# design.net
KiCad netlist of a schematic drawn in Altium Designer
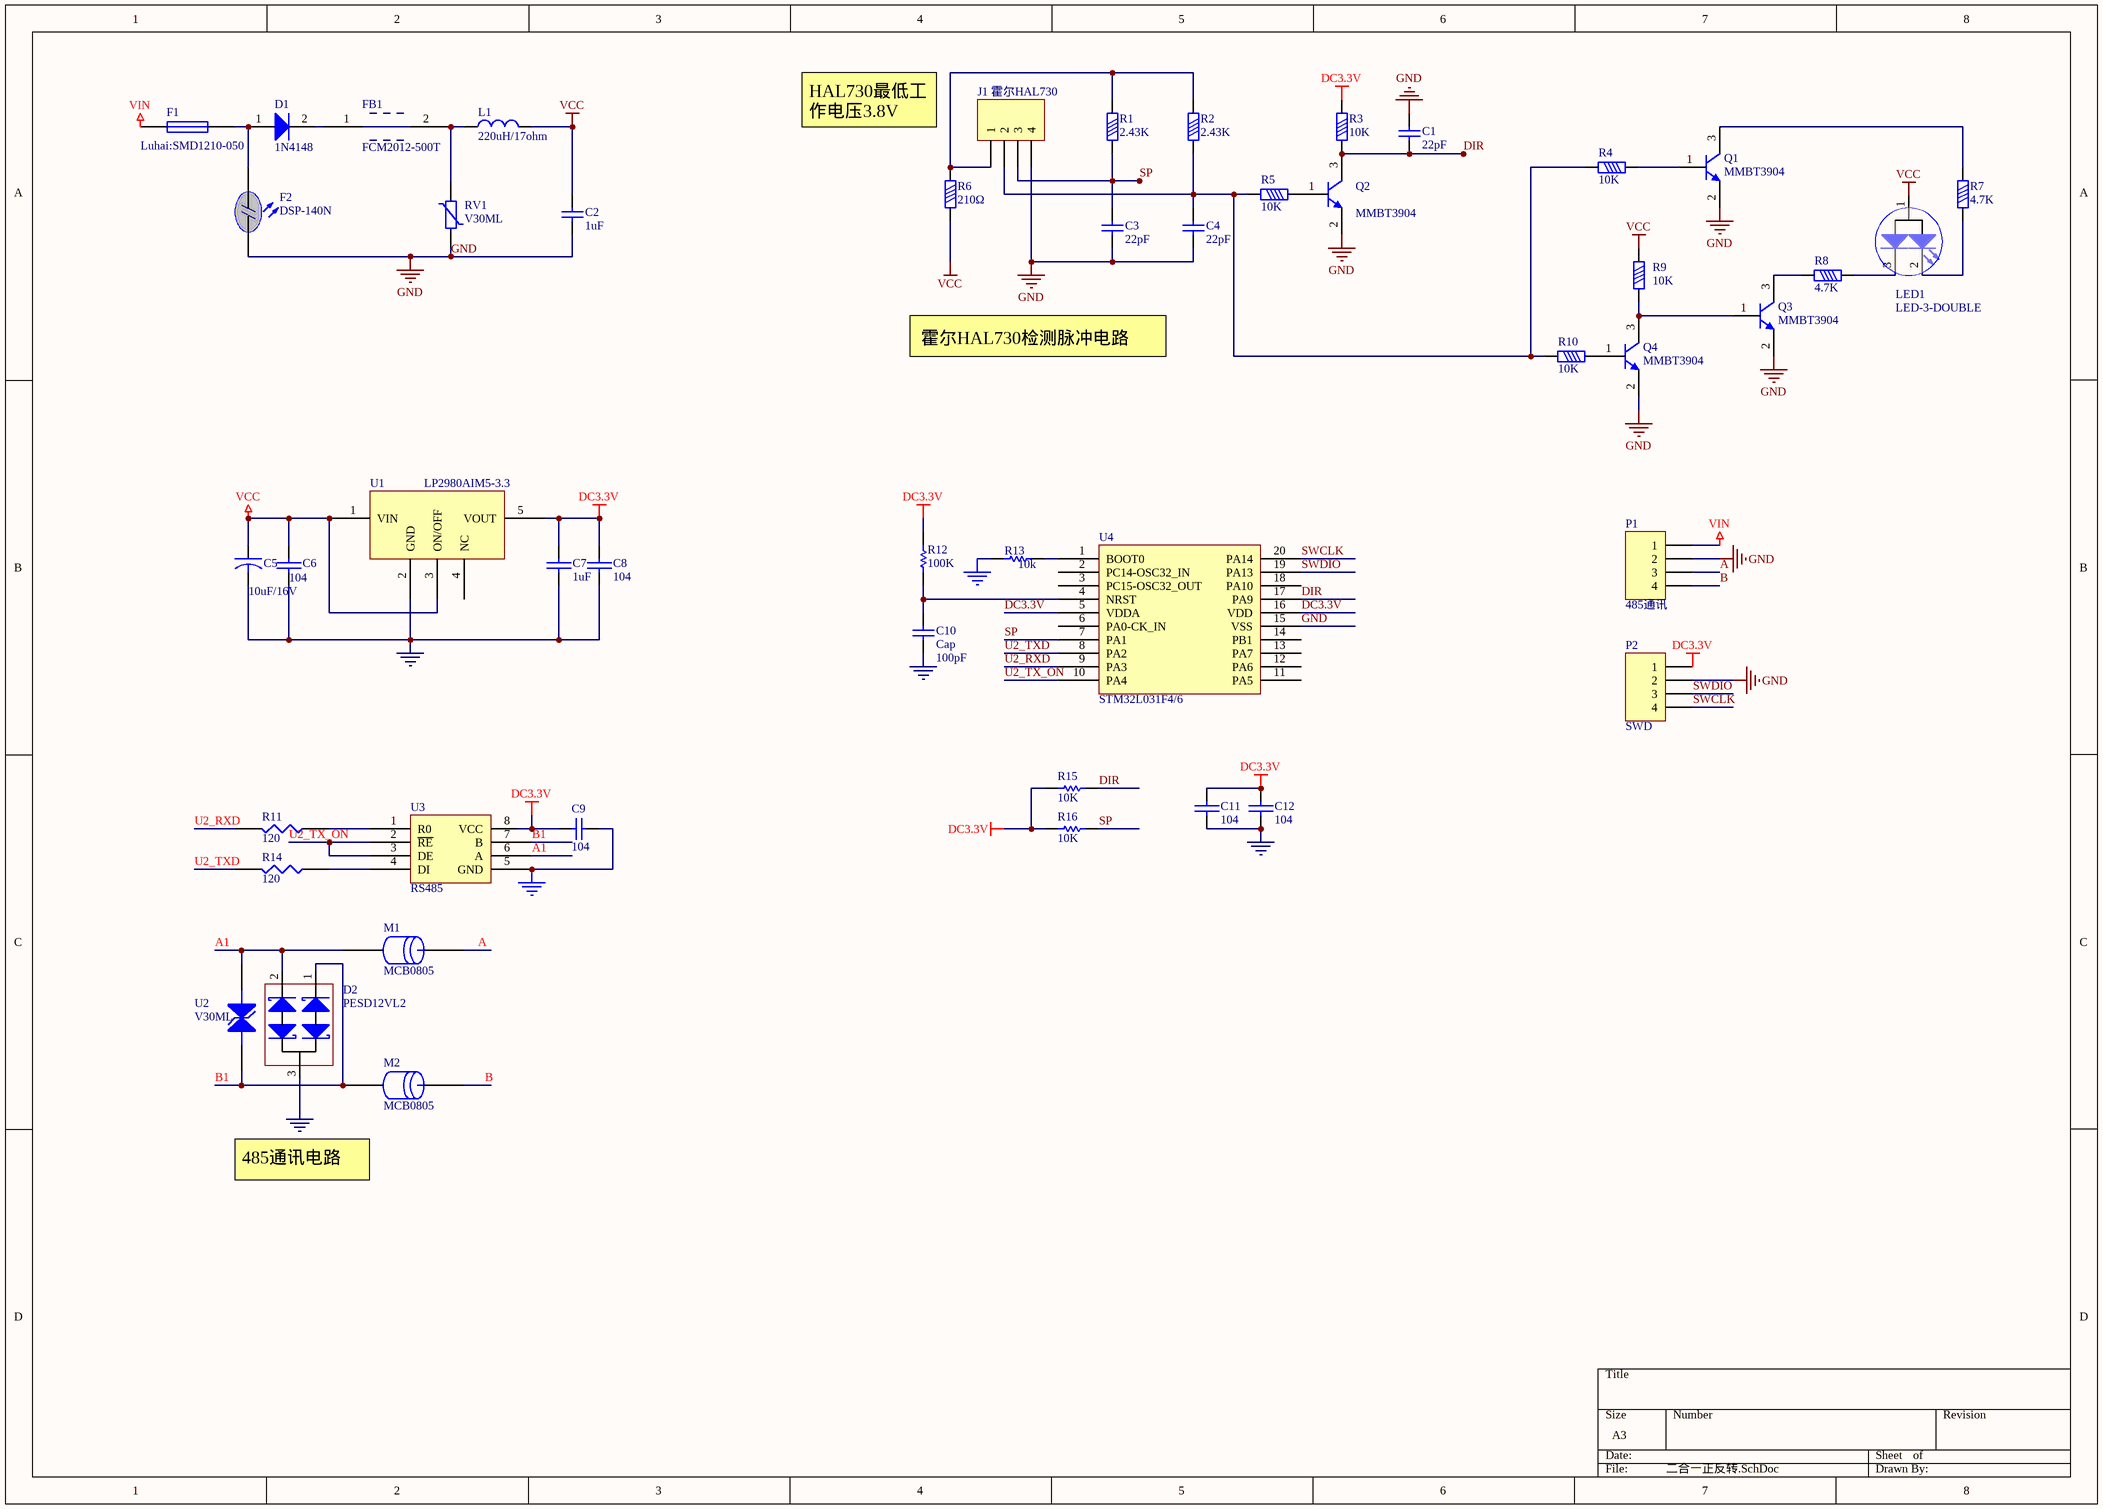
[diagram p0: 二合一正反转.SchDoc]

(export (version "E")
  (design (tool "Eeschema 10.0.6"))
  (components
    (comp (ref "C1")
      (value "22pF")
      (footprint "0603C")
      (description "Polarized Capacitor (Radial)")
      (fields (field (name "Comment") "Cap Chip 0603") (field (name "PUBLISHER") "Altium Limited"))
      (libsource (lib "EButterflyIntegratedLibrary") (part "Cap Chip 0603"))
    )
    (comp (ref "C2")
      (value "1uF")
      (footprint "0805C")
      (description "Polarized Capacitor (Radial)")
      (fields (field (name "PUBLISHER") "Altium Limited"))
      (libsource (lib "EButterflyIntegratedLibrary") (part "Cap Chip 0805"))
    )
    (comp (ref "C3")
      (value "22pF")
      (footprint "0603C")
      (description "Polarized Capacitor (Radial)")
      (fields (field (name "Comment") "Cap Chip 0603") (field (name "PUBLISHER") "Altium Limited"))
      (libsource (lib "EButterflyIntegratedLibrary") (part "Cap Chip 0603"))
    )
    (comp (ref "C4")
      (value "22pF")
      (footprint "0603C")
      (description "Polarized Capacitor (Radial)")
      (fields (field (name "Comment") "Cap Chip 0603") (field (name "PUBLISHER") "Altium Limited"))
      (libsource (lib "EButterflyIntegratedLibrary") (part "Cap Chip 0603"))
    )
    (comp (ref "C5")
      (value "10uF/16V")
      (footprint "A3216")
      (description "Capacitor")
      (libsource (lib "*") (part "CAPACITOR"))
    )
    (comp (ref "C6")
      (value "104")
      (footprint "0603C")
      (description "Capacitor")
      (libsource (lib "*") (part "CAP"))
    )
    (comp (ref "C7")
      (value "1uF")
      (footprint "0603C")
      (description "Capacitor")
      (libsource (lib "*") (part "CAP"))
    )
    (comp (ref "C8")
      (value "104")
      (footprint "0603C")
      (description "Capacitor")
      (libsource (lib "*") (part "CAP"))
    )
    (comp (ref "C9")
      (value "104")
      (footprint "0603C")
      (description "Capacitor")
      (fields (field (name "PUBLISHER") "*"))
      (libsource (lib "*") (part "Cap"))
    )
    (comp (ref "C10")
      (value "Cap")
      (footprint "0603C")
      (description "Capacitor")
      (fields (field (name "ALTIUM_VALUE") "100pF") (field (name "PUBLISHER") "Altium Limited"))
      (libsource (lib "Miscellaneous Devices") (part "Cap"))
    )
    (comp (ref "C11")
      (value "104")
      (footprint "0603C")
      (description "Capacitor")
      (libsource (lib "*") (part "CAP"))
    )
    (comp (ref "C12")
      (value "104")
      (footprint "0603C")
      (description "Capacitor")
      (libsource (lib "*") (part "CAP"))
    )
    (comp (ref "D1")
      (value "1N4148")
      (footprint "1N4148")
      (libsource (lib "Integrated_Library1") (part "1N4148"))
    )
    (comp (ref "D2") (value "PESD12VL2") (footprint "SOT23") (libsource (lib "lewis lib") (part "TVS")))
    (comp (ref "F1")
      (value "Luhai:SMD1210-050")
      (footprint "1210R")
      (description "Fuse")
      (fields (field (name "PUBLISHER") "Altium Limited"))
      (libsource (lib "Miscellaneous Devices") (part "Fuse 1"))
    )
    (comp (ref "F2")
      (value "DSP-140N")
      (footprint "DSP")
      (libsource (lib "Integrated_Library1") (part "DSP-140N"))
    )
    (comp (ref "FB1")
      (value "FCM2012-500T")
      (footprint "FB")
      (libsource (lib "Integrated_Library1") (part "FCM2012-500T"))
    )
    (comp (ref "J1")
      (value "霍尔HAL730")
      (footprint "HDR1X4")
      (description "Header, 4-Pin")
      (fields (field (name "PUBLISHER") "Altium Limited"))
      (libsource (lib "EButterflyIntegratedLibrary") (part "Header 4"))
    )
    (comp (ref "L1")
      (value "220uH/17ohm")
      (footprint "220uH/17ohm")
      (libsource (lib "Integrated_Library1") (part "220uH/17ohm"))
    )
    (comp (ref "LED1")
      (value "LED-3-DOUBLE")
      (footprint "LED-R3-H5-DOUBLE")
      (libsource (lib "Integrated_Library1") (part "DOUB-LED"))
    )
    (comp (ref "M1")
      (value "MCB0805")
      (footprint "0805F")
      (description "magnetic bead")
      (libsource (lib "lewis lib") (part "MAGNETIC BEAD"))
    )
    (comp (ref "M2")
      (value "MCB0805")
      (footprint "0805F")
      (description "magnetic bead")
      (libsource (lib "lewis lib") (part "MAGNETIC BEAD"))
    )
    (comp (ref "P1")
      (value "485通讯")
      (footprint "HDR1X4")
      (description "Header, 4-Pin, Right Angle")
      (fields (field (name "PUBLISHER") "Altium Limited"))
      (libsource (lib "Miscellaneous Connectors") (part "Header 4H"))
    )
    (comp (ref "P2")
      (value "SWD")
      (footprint "MHDR1X4")
      (description "Header, 4-Pin")
      (fields (field (name "PUBLISHER") "Altium Limited"))
      (libsource (lib "Miscellaneous Connectors") (part "Header 4"))
    )
    (comp (ref "Q1")
      (value "MMBT3904")
      (footprint "MMBT3904")
      (libsource (lib "Integrated_Library1") (part "MMBT3904"))
    )
    (comp (ref "Q2")
      (value "MMBT3904")
      (footprint "MMBT3904")
      (libsource (lib "Integrated_Library1") (part "MMBT3904"))
    )
    (comp (ref "Q3")
      (value "MMBT3904")
      (footprint "MMBT3904")
      (libsource (lib "Integrated_Library1") (part "MMBT3904"))
    )
    (comp (ref "Q4")
      (value "MMBT3904")
      (footprint "MMBT3904")
      (libsource (lib "Integrated_Library1") (part "MMBT3904"))
    )
    (comp (ref "R1")
      (value "2.43K")
      (footprint "0603C")
      (description "Resistor")
      (fields (field (name "Comment") "Resistor Chip 0603") (field (name "PUBLISHER") "Altium Limited"))
      (libsource (lib "") (part "Resistor Chip 0603_1"))
    )
    (comp (ref "R2")
      (value "2.43K")
      (footprint "0603C")
      (description "Resistor")
      (fields (field (name "Comment") "Resistor Chip 0603") (field (name "PUBLISHER") "Altium Limited"))
      (libsource (lib "") (part "Resistor Chip 0603_1"))
    )
    (comp (ref "R3")
      (value "10K")
      (footprint "0603C")
      (description "Resistor")
      (fields (field (name "Comment") "Resistor Chip 0603") (field (name "PUBLISHER") "Altium Limited"))
      (libsource (lib "") (part "Resistor Chip 0603_1"))
    )
    (comp (ref "R4")
      (value "10K")
      (footprint "0603C")
      (description "Resistor")
      (fields (field (name "Comment") "Resistor Chip 0603") (field (name "PUBLISHER") "Altium Limited"))
      (libsource (lib "EButterflyIntegratedLibrary") (part "Resistor Chip 0603"))
    )
    (comp (ref "R5")
      (value "10K")
      (footprint "0603C")
      (description "Resistor")
      (fields (field (name "Comment") "Resistor Chip 0603") (field (name "PUBLISHER") "Altium Limited"))
      (libsource (lib "EButterflyIntegratedLibrary") (part "Resistor Chip 0603"))
    )
    (comp (ref "R6")
      (value "210Ω")
      (footprint "0603C")
      (description "Resistor")
      (fields (field (name "Comment") "Resistor Chip 0603") (field (name "PUBLISHER") "Altium Limited"))
      (libsource (lib "") (part "Resistor Chip 0603_2"))
    )
    (comp (ref "R7")
      (value "4.7K")
      (footprint "0603C")
      (description "Resistor")
      (fields (field (name "Comment") "Resistor Chip 0603") (field (name "PUBLISHER") "Altium Limited"))
      (libsource (lib "") (part "Resistor Chip 0603_2"))
    )
    (comp (ref "R8")
      (value "4.7K")
      (footprint "0603C")
      (description "Resistor")
      (fields (field (name "Comment") "Resistor Chip 0603") (field (name "PUBLISHER") "Altium Limited"))
      (libsource (lib "EButterflyIntegratedLibrary") (part "Resistor Chip 0603"))
    )
    (comp (ref "R9")
      (value "10K")
      (footprint "0603C")
      (description "Resistor")
      (fields (field (name "Comment") "Resistor Chip 0603") (field (name "PUBLISHER") "Altium Limited"))
      (libsource (lib "") (part "Resistor Chip 0603_2"))
    )
    (comp (ref "R10")
      (value "10K")
      (footprint "0603C")
      (description "Resistor")
      (fields (field (name "Comment") "Resistor Chip 0603") (field (name "PUBLISHER") "Altium Limited"))
      (libsource (lib "EButterflyIntegratedLibrary") (part "Resistor Chip 0603"))
    )
    (comp (ref "R11") (value "120") (footprint "0603R") (libsource (lib "*") (part "RES1")))
    (comp (ref "R12")
      (value "100K")
      (footprint "0603R")
      (description "Resistor")
      (fields (field (name "PUBLISHER") "Altium Limited"))
      (libsource (lib "Miscellaneous Devices") (part "Res1"))
    )
    (comp (ref "R13")
      (value "10k")
      (footprint "0603R")
      (description "Resistor")
      (fields (field (name "PUBLISHER") "Altium Limited"))
      (libsource (lib "Miscellaneous Devices") (part "Res1"))
    )
    (comp (ref "R14") (value "120") (footprint "0603R") (libsource (lib "*") (part "RES1")))
    (comp (ref "R15")
      (value "10K")
      (footprint "0603R")
      (description "Resistor")
      (fields (field (name "PUBLISHER") "Altium Limited"))
      (libsource (lib "Miscellaneous Devices") (part "Res1"))
    )
    (comp (ref "R16")
      (value "10K")
      (footprint "0603R")
      (description "Resistor")
      (fields (field (name "PUBLISHER") "Altium Limited"))
      (libsource (lib "Miscellaneous Devices") (part "Res1"))
    )
    (comp (ref "RV1") (value "V30ML") (footprint "RV") (libsource (lib "Integrated_Library1") (part "V30ML")))
    (comp (ref "U1")
      (value "LP2980AIM5-3.3")
      (footprint "SOT-23-5")
      (libsource (lib "lewis lib") (part "LP2980AIM5-3.3"))
    )
    (comp (ref "U2") (value "V30ML") (footprint "0805C-E") (libsource (lib "*") (part "V30ML")))
    (comp (ref "U3") (value "RS485") (footprint "SO-8") (libsource (lib "*") (part "RS485")))
    (comp (ref "U4")
      (value "STM32L031F4/6")
      (footprint "TSSOP20")
      (libsource (lib "lewis lib") (part "STM32L031F4/6"))
    )
  )
  (nets
    (net (code "1") (name "/A") (class "Default")
      (node (ref "M1") (pin "2") (pintype "passive"))
      (node (ref "P1") (pin "3") (pinfunction "3_3") (pintype "passive"))
    )
    (net (code "2") (name "/A1") (class "Default")
      (node (ref "D2") (pin "2") (pinfunction "2_2") (pintype "passive"))
      (node (ref "M1") (pin "1") (pintype "passive"))
      (node (ref "U2") (pin "2") (pinfunction "2_2") (pintype "passive"))
      (node (ref "U3") (pin "6") (pinfunction "A_6") (pintype "passive"))
    )
    (net (code "3") (name "/B") (class "Default")
      (node (ref "M2") (pin "2") (pintype "passive"))
      (node (ref "P1") (pin "4") (pinfunction "4_4") (pintype "passive"))
    )
    (net (code "4") (name "/B1") (class "Default")
      (node (ref "D2") (pin "1") (pinfunction "1_1") (pintype "passive"))
      (node (ref "M2") (pin "1") (pintype "passive"))
      (node (ref "U2") (pin "1") (pinfunction "1_1") (pintype "passive"))
      (node (ref "U3") (pin "7") (pinfunction "B_7") (pintype "passive"))
    )
    (net (code "5") (name "/DIR") (class "Default")
      (node (ref "C1") (pin "1") (pinfunction "1_1") (pintype "passive"))
      (node (ref "Q2") (pin "3") (pinfunction "C_3") (pintype "passive"))
      (node (ref "R15") (pin "1") (pinfunction "1_1") (pintype "passive"))
      (node (ref "R3") (pin "1") (pinfunction "1_1") (pintype "passive"))
      (node (ref "U4") (pin "17") (pinfunction "PA9_17") (pintype "passive"))
    )
    (net (code "6") (name "/SP") (class "Default")
      (node (ref "C3") (pin "2") (pinfunction "2_2") (pintype "passive"))
      (node (ref "J1") (pin "3") (pinfunction "3_3") (pintype "passive"))
      (node (ref "R1") (pin "1") (pinfunction "1_1") (pintype "passive"))
      (node (ref "R16") (pin "2") (pinfunction "2_2") (pintype "passive"))
      (node (ref "U4") (pin "7") (pinfunction "PA1_7") (pintype "passive"))
    )
    (net (code "7") (name "/SWCLK") (class "Default")
      (node (ref "P2") (pin "4") (pinfunction "4_4") (pintype "passive"))
      (node (ref "U4") (pin "20") (pinfunction "PA14_20") (pintype "passive"))
    )
    (net (code "8") (name "/SWDIO") (class "Default")
      (node (ref "P2") (pin "3") (pinfunction "3_3") (pintype "passive"))
      (node (ref "U4") (pin "19") (pinfunction "PA13_19") (pintype "passive"))
    )
    (net (code "9") (name "/U2_RXD") (class "Default")
      (node (ref "R11") (pin "2") (pinfunction "2_2") (pintype "passive"))
      (node (ref "U4") (pin "9") (pinfunction "PA3_9") (pintype "passive"))
    )
    (net (code "10") (name "/U2_TXD") (class "Default")
      (node (ref "R14") (pin "2") (pinfunction "2_2") (pintype "passive"))
      (node (ref "U4") (pin "8") (pinfunction "PA2_8") (pintype "passive"))
    )
    (net (code "11") (name "/U2_TX_ON") (class "Default")
      (node (ref "U3") (pin "2") (pinfunction "~{RE}_2") (pintype "passive"))
      (node (ref "U3") (pin "3") (pinfunction "DE_3") (pintype "passive"))
      (node (ref "U4") (pin "10") (pinfunction "PA4_10") (pintype "passive"))
    )
    (net (code "12") (name "DC3.3V") (class "Default")
      (node (ref "C11") (pin "1") (pinfunction "1_1") (pintype "passive"))
      (node (ref "C12") (pin "1") (pinfunction "1_1") (pintype "passive"))
      (node (ref "C7") (pin "1") (pinfunction "1_1") (pintype "passive"))
      (node (ref "C8") (pin "1") (pinfunction "1_1") (pintype "passive"))
      (node (ref "C9") (pin "1") (pinfunction "1_1") (pintype "passive"))
      (node (ref "P2") (pin "1") (pinfunction "1_1") (pintype "passive"))
      (node (ref "R12") (pin "1") (pinfunction "1_1") (pintype "passive"))
      (node (ref "R15") (pin "2") (pinfunction "2_2") (pintype "passive"))
      (node (ref "R16") (pin "1") (pinfunction "1_1") (pintype "passive"))
      (node (ref "R3") (pin "2") (pinfunction "2_2") (pintype "passive"))
      (node (ref "U1") (pin "5") (pinfunction "VOUT_5") (pintype "passive"))
      (node (ref "U3") (pin "8") (pinfunction "VCC_8") (pintype "passive"))
      (node (ref "U4") (pin "16") (pinfunction "VDD_16") (pintype "passive"))
      (node (ref "U4") (pin "5") (pinfunction "VDDA_5") (pintype "passive"))
    )
    (net (code "13") (name "GND") (class "Default")
      (node (ref "C1") (pin "2") (pinfunction "2_2") (pintype "passive"))
      (node (ref "C10") (pin "1") (pinfunction "1_1") (pintype "passive"))
      (node (ref "C11") (pin "2") (pinfunction "2_2") (pintype "passive"))
      (node (ref "C12") (pin "2") (pinfunction "2_2") (pintype "passive"))
      (node (ref "C2") (pin "1") (pinfunction "1_1") (pintype "passive"))
      (node (ref "C3") (pin "1") (pinfunction "1_1") (pintype "passive"))
      (node (ref "C4") (pin "1") (pinfunction "1_1") (pintype "passive"))
      (node (ref "C5") (pin "2") (pinfunction "2_2") (pintype "passive"))
      (node (ref "C6") (pin "2") (pinfunction "2_2") (pintype "passive"))
      (node (ref "C7") (pin "2") (pinfunction "2_2") (pintype "passive"))
      (node (ref "C8") (pin "2") (pinfunction "2_2") (pintype "passive"))
      (node (ref "C9") (pin "2") (pinfunction "2_2") (pintype "passive"))
      (node (ref "D2") (pin "3") (pinfunction "3_3") (pintype "passive"))
      (node (ref "F2") (pin "2") (pinfunction "2_2") (pintype "passive"))
      (node (ref "J1") (pin "4") (pinfunction "4_4") (pintype "passive"))
      (node (ref "P1") (pin "2") (pinfunction "2_2") (pintype "passive"))
      (node (ref "P2") (pin "2") (pinfunction "2_2") (pintype "passive"))
      (node (ref "Q1") (pin "2") (pinfunction "E_2") (pintype "passive"))
      (node (ref "Q2") (pin "2") (pinfunction "E_2") (pintype "passive"))
      (node (ref "Q3") (pin "2") (pinfunction "E_2") (pintype "passive"))
      (node (ref "Q4") (pin "2") (pinfunction "E_2") (pintype "passive"))
      (node (ref "R13") (pin "2") (pinfunction "2_2") (pintype "passive"))
      (node (ref "RV1") (pin "1") (pinfunction "1_1") (pintype "passive"))
      (node (ref "U1") (pin "2") (pinfunction "GND_2") (pintype "passive"))
      (node (ref "U3") (pin "5") (pinfunction "GND_5") (pintype "passive"))
      (node (ref "U4") (pin "15") (pinfunction "VSS_15") (pintype "passive"))
    )
    (net (code "14") (name "Net-(C4-Pad2)") (class "Default")
      (node (ref "C4") (pin "2") (pinfunction "2_2") (pintype "passive"))
      (node (ref "J1") (pin "2") (pinfunction "2_2") (pintype "passive"))
      (node (ref "R10") (pin "2") (pinfunction "2_2") (pintype "passive"))
      (node (ref "R2") (pin "1") (pinfunction "1_1") (pintype "passive"))
      (node (ref "R4") (pin "2") (pinfunction "2_2") (pintype "passive"))
      (node (ref "R5") (pin "2") (pinfunction "2_2") (pintype "passive"))
    )
    (net (code "15") (name "Net-(D1-A)") (class "Default")
      (node (ref "D1") (pin "1") (pinfunction "A_1") (pintype "passive"))
      (node (ref "F1") (pin "2") (pinfunction "2_2") (pintype "passive"))
      (node (ref "F2") (pin "1") (pinfunction "1_1") (pintype "passive"))
    )
    (net (code "16") (name "Net-(D1-K)") (class "Default")
      (node (ref "D1") (pin "2") (pinfunction "K_2") (pintype "passive"))
      (node (ref "FB1") (pin "1") (pinfunction "1_1") (pintype "passive"))
    )
    (net (code "17") (name "Net-(FB1-Pad2)") (class "Default")
      (node (ref "FB1") (pin "2") (pinfunction "2_2") (pintype "passive"))
      (node (ref "L1") (pin "1") (pinfunction "1_1") (pintype "passive"))
      (node (ref "RV1") (pin "2") (pinfunction "2_2") (pintype "passive"))
    )
    (net (code "18") (name "Net-(J1-Pad1)") (class "Default")
      (node (ref "J1") (pin "1") (pinfunction "1_1") (pintype "passive"))
      (node (ref "R1") (pin "2") (pinfunction "2_2") (pintype "passive"))
      (node (ref "R2") (pin "2") (pinfunction "2_2") (pintype "passive"))
      (node (ref "R6") (pin "1") (pinfunction "1_1") (pintype "passive"))
    )
    (net (code "19") (name "Net-(LED1-A-Pad2)") (class "Default")
      (node (ref "LED1") (pin "2") (pinfunction "A_2") (pintype "passive"))
      (node (ref "R7") (pin "2") (pinfunction "2_2") (pintype "passive"))
    )
    (net (code "20") (name "Net-(LED1-A-Pad3)") (class "Default")
      (node (ref "LED1") (pin "3") (pinfunction "A_3") (pintype "passive"))
      (node (ref "R8") (pin "1") (pinfunction "1_1") (pintype "passive"))
    )
    (net (code "21") (name "Net-(Q1-B)") (class "Default")
      (node (ref "Q1") (pin "1") (pinfunction "B_1") (pintype "passive"))
      (node (ref "R4") (pin "1") (pinfunction "1_1") (pintype "passive"))
    )
    (net (code "22") (name "Net-(Q1-C)") (class "Default")
      (node (ref "Q1") (pin "3") (pinfunction "C_3") (pintype "passive"))
      (node (ref "R7") (pin "1") (pinfunction "1_1") (pintype "passive"))
    )
    (net (code "23") (name "Net-(Q2-B)") (class "Default")
      (node (ref "Q2") (pin "1") (pinfunction "B_1") (pintype "passive"))
      (node (ref "R5") (pin "1") (pinfunction "1_1") (pintype "passive"))
    )
    (net (code "24") (name "Net-(Q3-B)") (class "Default")
      (node (ref "Q3") (pin "1") (pinfunction "B_1") (pintype "passive"))
      (node (ref "Q4") (pin "3") (pinfunction "C_3") (pintype "passive"))
      (node (ref "R9") (pin "2") (pinfunction "2_2") (pintype "passive"))
    )
    (net (code "25") (name "Net-(Q3-C)") (class "Default")
      (node (ref "Q3") (pin "3") (pinfunction "C_3") (pintype "passive"))
      (node (ref "R8") (pin "2") (pinfunction "2_2") (pintype "passive"))
    )
    (net (code "26") (name "Net-(Q4-B)") (class "Default")
      (node (ref "Q4") (pin "1") (pinfunction "B_1") (pintype "passive"))
      (node (ref "R10") (pin "1") (pinfunction "1_1") (pintype "passive"))
    )
    (net (code "27") (name "Net-(U3-DI)") (class "Default")
      (node (ref "R14") (pin "1") (pinfunction "1_1") (pintype "passive"))
      (node (ref "U3") (pin "4") (pinfunction "DI_4") (pintype "passive"))
    )
    (net (code "28") (name "Net-(U3-R0)") (class "Default")
      (node (ref "R11") (pin "1") (pinfunction "1_1") (pintype "passive"))
      (node (ref "U3") (pin "1") (pinfunction "R0_1") (pintype "passive"))
    )
    (net (code "29") (name "Net-(U4-BOOT0)") (class "Default")
      (node (ref "R13") (pin "1") (pinfunction "1_1") (pintype "passive"))
      (node (ref "U4") (pin "1") (pinfunction "BOOT0_1") (pintype "passive"))
    )
    (net (code "30") (name "Net-(U4-NRST)") (class "Default")
      (node (ref "C10") (pin "2") (pinfunction "2_2") (pintype "passive"))
      (node (ref "R12") (pin "2") (pinfunction "2_2") (pintype "passive"))
      (node (ref "U4") (pin "4") (pinfunction "NRST_4") (pintype "passive"))
    )
    (net (code "31") (name "VCC") (class "Default")
      (node (ref "C2") (pin "2") (pinfunction "2_2") (pintype "passive"))
      (node (ref "C5") (pin "1") (pinfunction "1_1") (pintype "passive"))
      (node (ref "C6") (pin "1") (pinfunction "1_1") (pintype "passive"))
      (node (ref "L1") (pin "2") (pinfunction "2_2") (pintype "passive"))
      (node (ref "LED1") (pin "1") (pinfunction "K_1") (pintype "passive"))
      (node (ref "R6") (pin "2") (pinfunction "2_2") (pintype "passive"))
      (node (ref "R9") (pin "1") (pinfunction "1_1") (pintype "passive"))
      (node (ref "U1") (pin "1") (pinfunction "VIN_1") (pintype "passive"))
      (node (ref "U1") (pin "3") (pinfunction "ON/OFF_3") (pintype "passive"))
    )
    (net (code "32") (name "VIN") (class "Default")
      (node (ref "F1") (pin "1") (pinfunction "1_1") (pintype "passive"))
      (node (ref "P1") (pin "1") (pinfunction "1_1") (pintype "passive"))
    )
    (net (code "33") (name "unconnected-(U1-NC-Pad4)") (class "Default")
      (node (ref "U1") (pin "4") (pinfunction "NC_4") (pintype "passive"))
    )
    (net (code "34") (name "unconnected-(U4-PA0-CK_IN-Pad6)") (class "Default")
      (node (ref "U4") (pin "6") (pinfunction "PA0-CK_IN_6") (pintype "passive"))
    )
    (net (code "35") (name "unconnected-(U4-PA5-Pad11)") (class "Default")
      (node (ref "U4") (pin "11") (pinfunction "PA5_11") (pintype "passive"))
    )
    (net (code "36") (name "unconnected-(U4-PA6-Pad12)") (class "Default")
      (node (ref "U4") (pin "12") (pinfunction "PA6_12") (pintype "passive"))
    )
    (net (code "37") (name "unconnected-(U4-PA7-Pad13)") (class "Default")
      (node (ref "U4") (pin "13") (pinfunction "PA7_13") (pintype "passive"))
    )
    (net (code "38") (name "unconnected-(U4-PA10-Pad18)") (class "Default")
      (node (ref "U4") (pin "18") (pinfunction "PA10_18") (pintype "passive"))
    )
    (net (code "39") (name "unconnected-(U4-PB1-Pad14)") (class "Default")
      (node (ref "U4") (pin "14") (pinfunction "PB1_14") (pintype "passive"))
    )
    (net (code "40") (name "unconnected-(U4-PC14-OSC32_IN-Pad2)") (class "Default")
      (node (ref "U4") (pin "2") (pinfunction "PC14-OSC32_IN_2") (pintype "passive"))
    )
    (net (code "41") (name "unconnected-(U4-PC15-OSC32_OUT-Pad3)") (class "Default")
      (node (ref "U4") (pin "3") (pinfunction "PC15-OSC32_OUT_3") (pintype "passive"))
    )
  )
)
